# XL4432-SMT3.net
KiCad netlist of a schematic drawn in EAGLE
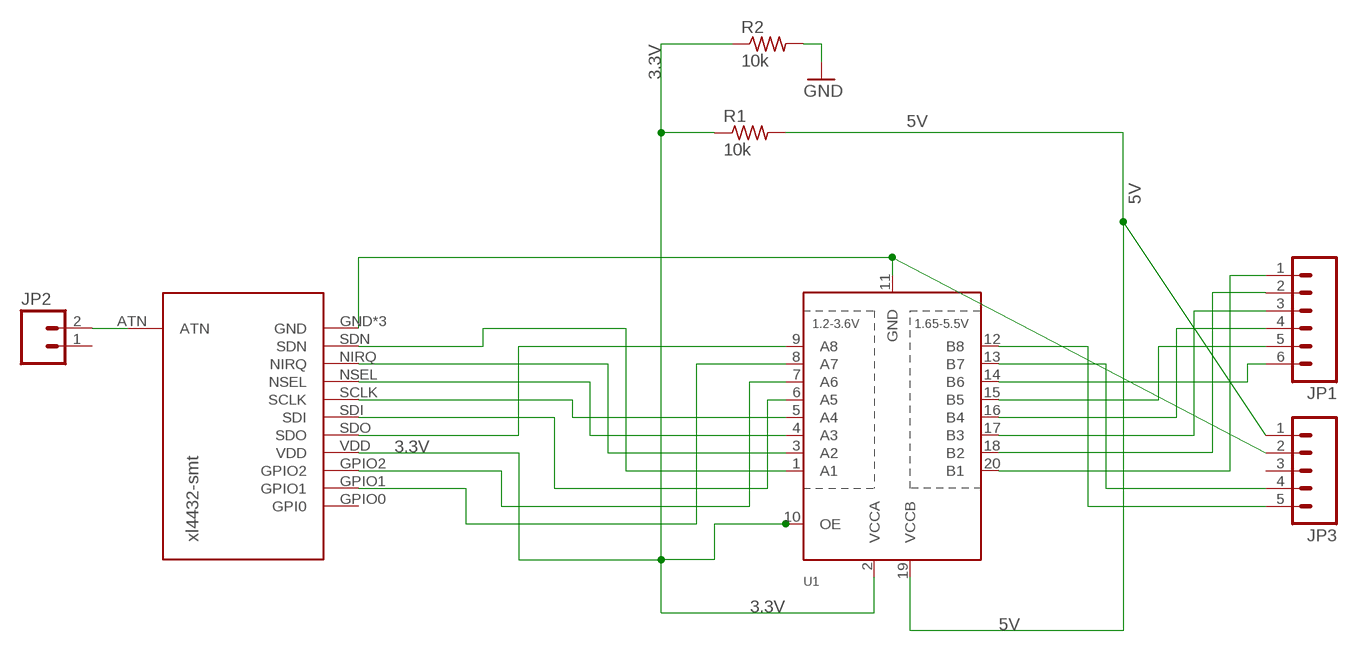
[diagram p0: schematic, sheet 1]

(export (version "E")
  (design (tool "Eeschema 10.0.6"))
  (components
    (comp (ref "JP1")
      (value "M06LOCK")
      (footprint "eagle-import:1X06_LOCK")
      (libsource (lib "eagle-import") (part "M06LOCK"))
    )
    (comp (ref "JP2")
      (value "M02LOCK")
      (footprint "eagle-import:1X02_LOCK")
      (libsource (lib "eagle-import") (part "M02LOCK"))
    )
    (comp (ref "JP3")
      (value "M05LOCK")
      (footprint "eagle-import:1X05_LOCK")
      (libsource (lib "eagle-import") (part "M05LOCK"))
    )
    (comp (ref "R1")
      (value "10k")
      (footprint "eagle-import:R0805")
      (libsource (lib "eagle-import") (part "R-US_R0805"))
    )
    (comp (ref "R2")
      (value "10k")
      (footprint "eagle-import:R0805")
      (libsource (lib "eagle-import") (part "R-US_R0805"))
    )
    (comp (ref "U$1")
      (value "XL4432-SMT")
      (footprint "eagle-import:XL4432-SMT")
      (libsource (lib "eagle-import") (part "XL4432-SMT"))
    )
    (comp (ref "U1")
      (value "TXB0108PWR")
      (footprint "eagle-import:TSSOP20")
      (libsource (lib "eagle-import") (part "TXB0108PWR"))
    )
  )
  (nets
    (net (code "1") (name "/3.3V") (class "Default")
      (node (ref "R1") (pin "1") (pinfunction "1_1") (pintype "passive"))
      (node (ref "R2") (pin "1") (pinfunction "1_1") (pintype "passive"))
      (node (ref "U$1") (pin "VDD") (pinfunction "VDD_VDD") (pintype "bidirectional"))
      (node (ref "U1") (pin "10") (pinfunction "OE_10") (pintype "bidirectional"))
      (node (ref "U1") (pin "2") (pinfunction "VCCA_2") (pintype "bidirectional"))
    )
    (net (code "2") (name "/5V") (class "Default")
      (node (ref "JP3") (pin "1") (pinfunction "1_1") (pintype "passive"))
      (node (ref "R1") (pin "2") (pinfunction "2_2") (pintype "passive"))
      (node (ref "U1") (pin "19") (pinfunction "VCCB_19") (pintype "bidirectional"))
    )
    (net (code "3") (name "GND") (class "Default")
      (node (ref "JP3") (pin "2") (pinfunction "2_2") (pintype "passive"))
      (node (ref "R2") (pin "2") (pinfunction "2_2") (pintype "passive"))
      (node (ref "U$1") (pin "GND") (pinfunction "GND_GND") (pintype "bidirectional"))
      (node (ref "U$1") (pin "GND1") (pinfunction "GND_GND1") (pintype "bidirectional"))
      (node (ref "U$1") (pin "GND3") (pinfunction "GND_GND3") (pintype "bidirectional"))
      (node (ref "U1") (pin "11") (pinfunction "GND_11") (pintype "bidirectional"))
    )
    (net (code "4") (name "Net-(JP2-Pad2)") (class "Default")
      (node (ref "JP2") (pin "2") (pinfunction "2_2") (pintype "passive"))
      (node (ref "U$1") (pin "ATN") (pinfunction "ATN_ATN") (pintype "bidirectional"))
    )
    (net (code "5") (name "Net-(U1-A1)") (class "Default")
      (node (ref "U$1") (pin "SDN") (pinfunction "SDN_SDN") (pintype "bidirectional"))
      (node (ref "U1") (pin "1") (pinfunction "A1_1") (pintype "bidirectional"))
    )
    (net (code "6") (name "Net-(U1-A2)") (class "Default")
      (node (ref "U$1") (pin "NIRQ") (pinfunction "NIRQ_NIRQ") (pintype "bidirectional"))
      (node (ref "U1") (pin "3") (pinfunction "A2_3") (pintype "bidirectional"))
    )
    (net (code "7") (name "Net-(U1-A3)") (class "Default")
      (node (ref "U$1") (pin "NSEL") (pinfunction "NSEL_NSEL") (pintype "bidirectional"))
      (node (ref "U1") (pin "4") (pinfunction "A3_4") (pintype "bidirectional"))
    )
    (net (code "8") (name "Net-(U1-A4)") (class "Default")
      (node (ref "U$1") (pin "SCLK") (pinfunction "SCLK_SCLK") (pintype "bidirectional"))
      (node (ref "U1") (pin "5") (pinfunction "A4_5") (pintype "bidirectional"))
    )
    (net (code "9") (name "Net-(U1-A5)") (class "Default")
      (node (ref "U$1") (pin "SDI") (pinfunction "SDI_SDI") (pintype "bidirectional"))
      (node (ref "U1") (pin "6") (pinfunction "A5_6") (pintype "bidirectional"))
    )
    (net (code "10") (name "Net-(U1-A6)") (class "Default")
      (node (ref "U$1") (pin "GPIO2") (pinfunction "GPIO2_GPIO2") (pintype "bidirectional"))
      (node (ref "U1") (pin "7") (pinfunction "A6_7") (pintype "bidirectional"))
    )
    (net (code "11") (name "Net-(U1-A7)") (class "Default")
      (node (ref "U$1") (pin "GPIO1") (pinfunction "GPIO1_GPIO1") (pintype "bidirectional"))
      (node (ref "U1") (pin "8") (pinfunction "A7_8") (pintype "bidirectional"))
    )
    (net (code "12") (name "Net-(U1-A8)") (class "Default")
      (node (ref "U$1") (pin "SDO") (pinfunction "SDO_SDO") (pintype "bidirectional"))
      (node (ref "U1") (pin "9") (pinfunction "A8_9") (pintype "bidirectional"))
    )
    (net (code "13") (name "Net-(U1-B1)") (class "Default")
      (node (ref "JP1") (pin "1") (pinfunction "1_1") (pintype "passive"))
      (node (ref "U1") (pin "20") (pinfunction "B1_20") (pintype "bidirectional"))
    )
    (net (code "14") (name "Net-(U1-B2)") (class "Default")
      (node (ref "JP1") (pin "2") (pinfunction "2_2") (pintype "passive"))
      (node (ref "U1") (pin "18") (pinfunction "B2_18") (pintype "bidirectional"))
    )
    (net (code "15") (name "Net-(U1-B3)") (class "Default")
      (node (ref "JP1") (pin "3") (pinfunction "3_3") (pintype "passive"))
      (node (ref "U1") (pin "17") (pinfunction "B3_17") (pintype "bidirectional"))
    )
    (net (code "16") (name "Net-(U1-B4)") (class "Default")
      (node (ref "JP1") (pin "4") (pinfunction "4_4") (pintype "passive"))
      (node (ref "U1") (pin "16") (pinfunction "B4_16") (pintype "bidirectional"))
    )
    (net (code "17") (name "Net-(U1-B5)") (class "Default")
      (node (ref "JP1") (pin "5") (pinfunction "5_5") (pintype "passive"))
      (node (ref "U1") (pin "15") (pinfunction "B5_15") (pintype "bidirectional"))
    )
    (net (code "18") (name "Net-(U1-B6)") (class "Default")
      (node (ref "JP1") (pin "6") (pinfunction "6_6") (pintype "passive"))
      (node (ref "U1") (pin "14") (pinfunction "B6_14") (pintype "bidirectional"))
    )
    (net (code "19") (name "Net-(U1-B7)") (class "Default")
      (node (ref "JP3") (pin "4") (pinfunction "4_4") (pintype "passive"))
      (node (ref "U1") (pin "13") (pinfunction "B7_13") (pintype "bidirectional"))
    )
    (net (code "20") (name "Net-(U1-B8)") (class "Default")
      (node (ref "JP3") (pin "5") (pinfunction "5_5") (pintype "passive"))
      (node (ref "U1") (pin "12") (pinfunction "B8_12") (pintype "bidirectional"))
    )
    (net (code "21") (name "unconnected-(JP2-Pad1)") (class "Default")
      (node (ref "JP2") (pin "1") (pinfunction "1_1") (pintype "passive"))
    )
    (net (code "22") (name "unconnected-(JP3-Pad3)") (class "Default")
      (node (ref "JP3") (pin "3") (pinfunction "3_3") (pintype "passive"))
    )
    (net (code "23") (name "unconnected-(U$1-GPI0-PadGPIO0)") (class "Default")
      (node (ref "U$1") (pin "GPIO0") (pinfunction "GPI0_GPIO0") (pintype "bidirectional"))
    )
  )
)
